# 2.net
KiCad netlist of a schematic drawn in Altium Designer
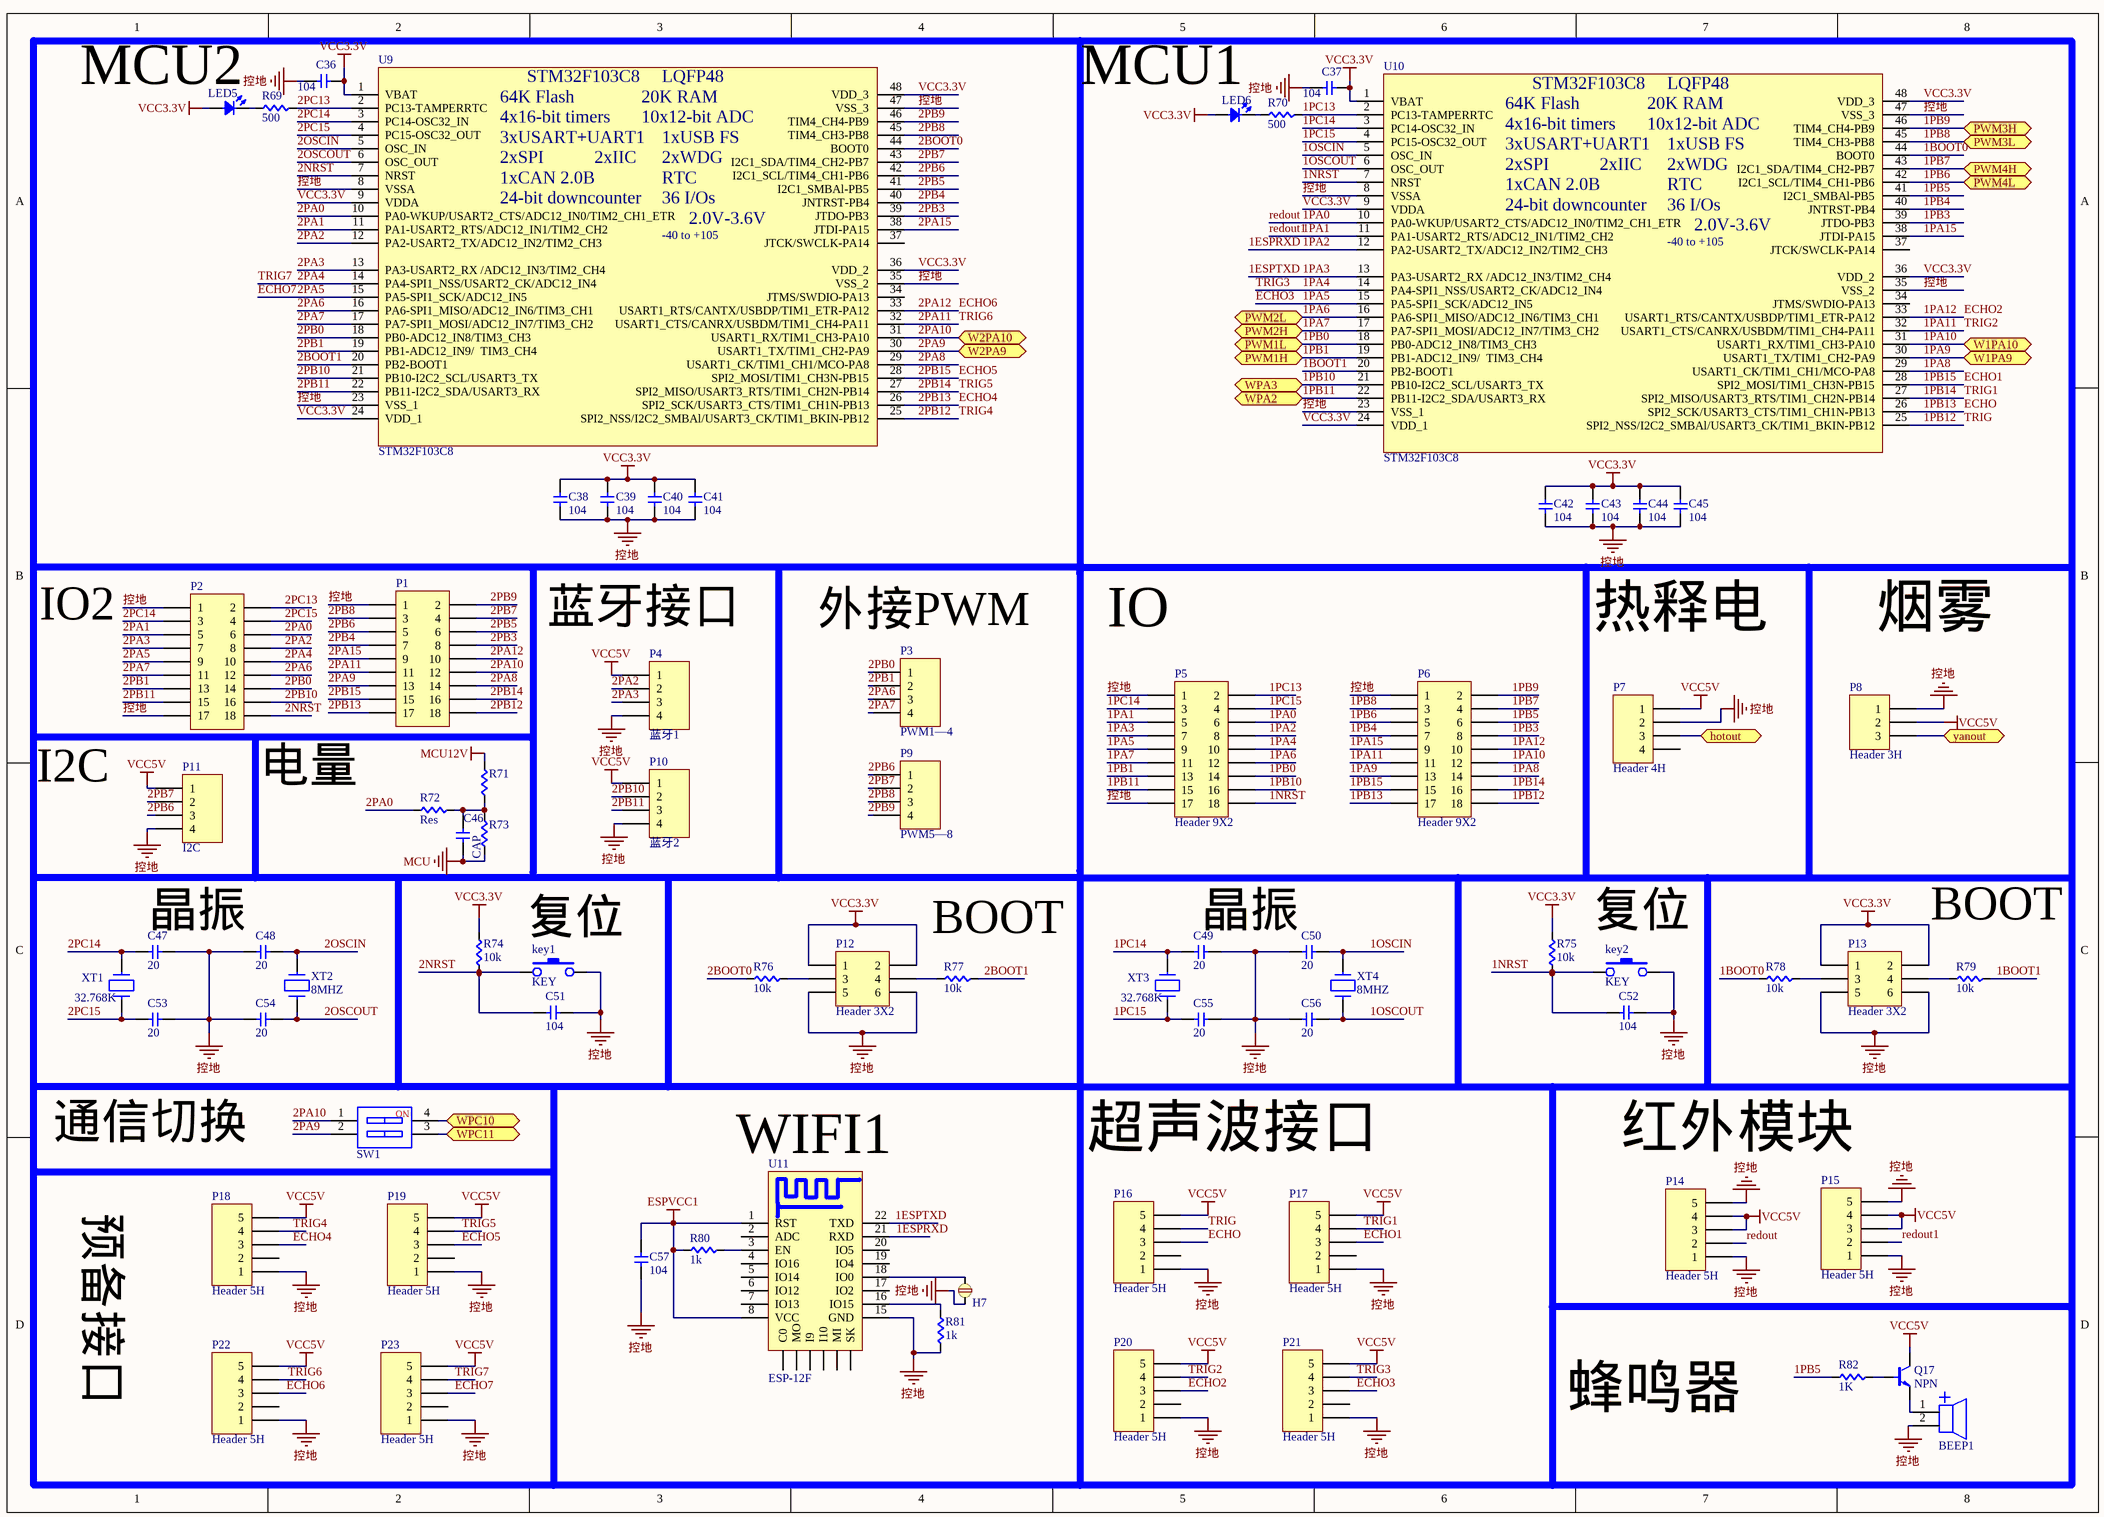
[diagram p0: 小车主板原理图2.SchDoc]

(export (version "E")
  (design (tool "Eeschema 10.0.6"))
  (components
    (comp (ref "BEEP1") (value "5V有源蜂鸣器") (footprint "5V蜂鸣器") (libsource (lib "史福祥库") (part "5V有源蜂鸣器")))
    (comp (ref "C36") (value "104") (footprint "0805C") (libsource (lib "史福祥库") (part "C")))
    (comp (ref "C37") (value "104") (footprint "0805C") (libsource (lib "史福祥库") (part "C")))
    (comp (ref "C38") (value "104") (footprint "0805C") (libsource (lib "史福祥库") (part "C")))
    (comp (ref "C39") (value "104") (footprint "0805C") (libsource (lib "史福祥库") (part "C")))
    (comp (ref "C40") (value "104") (footprint "0805C") (libsource (lib "史福祥库") (part "C")))
    (comp (ref "C41") (value "104") (footprint "0805C") (libsource (lib "史福祥库") (part "C")))
    (comp (ref "C42") (value "104") (footprint "0805C") (libsource (lib "史福祥库") (part "C")))
    (comp (ref "C43") (value "104") (footprint "0805C") (libsource (lib "史福祥库") (part "C")))
    (comp (ref "C44") (value "104") (footprint "0805C") (libsource (lib "史福祥库") (part "C")))
    (comp (ref "C45") (value "104") (footprint "0805C") (libsource (lib "史福祥库") (part "C")))
    (comp (ref "C46") (value "CAP") (footprint "0805C") (libsource (lib "史福祥库") (part "C")))
    (comp (ref "C47") (value "20") (footprint "0805C") (libsource (lib "史福祥库") (part "C")))
    (comp (ref "C48") (value "20") (footprint "0805C") (libsource (lib "史福祥库") (part "C")))
    (comp (ref "C49") (value "20") (footprint "0805C") (libsource (lib "史福祥库") (part "C")))
    (comp (ref "C50") (value "20") (footprint "0805C") (libsource (lib "史福祥库") (part "C")))
    (comp (ref "C51") (value "104") (footprint "0805C") (libsource (lib "史福祥库") (part "C")))
    (comp (ref "C52") (value "104") (footprint "0805C") (libsource (lib "史福祥库") (part "C")))
    (comp (ref "C53") (value "20") (footprint "0805C") (libsource (lib "史福祥库") (part "C")))
    (comp (ref "C54") (value "20") (footprint "0805C") (libsource (lib "史福祥库") (part "C")))
    (comp (ref "C55") (value "20") (footprint "0805C") (libsource (lib "史福祥库") (part "C")))
    (comp (ref "C56") (value "20") (footprint "0805C") (libsource (lib "史福祥库") (part "C")))
    (comp (ref "C57") (value "104") (footprint "0805C") (libsource (lib "史福祥库") (part "C")))
    (comp (ref "H7") (value "2脚") (footprint "2P") (libsource (lib "史福祥库") (part "2脚")))
    (comp (ref "key1") (value "KEY") (footprint "按键DIP-3*6*5") (libsource (lib "史福祥库") (part "KEY")))
    (comp (ref "key2") (value "KEY") (footprint "按键DIP-3*6*5") (libsource (lib "史福祥库") (part "KEY")))
    (comp (ref "LED5")
      (value "LED")
      (footprint "0805D")
      (fields (field (name "PUBLISHER") "Altium Limited"))
      (libsource (lib "史福祥库") (part "LED"))
    )
    (comp (ref "LED6")
      (value "LED")
      (footprint "0805D")
      (fields (field (name "PUBLISHER") "Altium Limited"))
      (libsource (lib "史福祥库") (part "LED"))
    )
    (comp (ref "P1")
      (value "~")
      (footprint "HDR2X9")
      (description "Header, 9-Pin, Dual row")
      (fields (field (name "PUBLISHER") "Altium Limited"))
      (libsource (lib "Miscellaneous Connectors") (part "Header 9X2"))
    )
    (comp (ref "P2")
      (value "~")
      (footprint "HDR2X9")
      (description "Header, 9-Pin, Dual row")
      (fields (field (name "PUBLISHER") "Altium Limited"))
      (libsource (lib "Miscellaneous Connectors") (part "Header 9X2"))
    )
    (comp (ref "P3")
      (value "PWM1—4")
      (footprint "PZ_XH-2.54-4P")
      (description "Header, 4-Pin, Right Angle")
      (fields (field (name "PUBLISHER") "Altium Limited"))
      (libsource (lib "") (part "Header 4H_1"))
    )
    (comp (ref "P4")
      (value "蓝牙1")
      (footprint "PZ_XH-2.54-4P")
      (description "Header, 4-Pin, Right Angle")
      (fields (field (name "PUBLISHER") "Altium Limited"))
      (libsource (lib "") (part "Header 4H_1"))
    )
    (comp (ref "P5")
      (value "Header 9X2")
      (footprint "HDR2X9")
      (description "Header, 9-Pin, Dual row")
      (fields (field (name "PUBLISHER") "Altium Limited"))
      (libsource (lib "Miscellaneous Connectors") (part "Header 9X2"))
    )
    (comp (ref "P6")
      (value "Header 9X2")
      (footprint "HDR2X9")
      (description "Header, 9-Pin, Dual row")
      (fields (field (name "PUBLISHER") "Altium Limited"))
      (libsource (lib "Miscellaneous Connectors") (part "Header 9X2"))
    )
    (comp (ref "P7")
      (value "Header 4H")
      (footprint "PZ_XH-2.54-4P")
      (description "Header, 4-Pin, Right Angle")
      (fields (field (name "PUBLISHER") "Altium Limited"))
      (libsource (lib "Miscellaneous Connectors") (part "Header 4H"))
    )
    (comp (ref "P8")
      (value "Header 3H")
      (footprint "PZ_XH-2.54-3P")
      (description "Header, 3-Pin, Right Angle")
      (fields (field (name "PUBLISHER") "Altium Limited"))
      (libsource (lib "Miscellaneous Connectors") (part "Header 3H"))
    )
    (comp (ref "P9")
      (value "PWM5—8")
      (footprint "PZ_XH-2.54-4P")
      (description "Header, 4-Pin, Right Angle")
      (fields (field (name "PUBLISHER") "Altium Limited"))
      (libsource (lib "") (part "Header 4H_1"))
    )
    (comp (ref "P10")
      (value "蓝牙2")
      (footprint "PZ_XH-2.54-4P")
      (description "Header, 4-Pin, Right Angle")
      (fields (field (name "PUBLISHER") "Altium Limited"))
      (libsource (lib "") (part "Header 4H_1"))
    )
    (comp (ref "P11")
      (value "I2C")
      (footprint "PZ_XH-2.54-4P")
      (description "Header, 4-Pin, Right Angle")
      (fields (field (name "PUBLISHER") "Altium Limited"))
      (libsource (lib "") (part "Header 4H_1"))
    )
    (comp (ref "P12")
      (value "Header 3X2")
      (footprint "HDR2X3")
      (description "Header, 3-Pin, Dual row")
      (fields (field (name "PUBLISHER") "Altium Limited"))
      (libsource (lib "Miscellaneous Connectors") (part "Header 3X2"))
    )
    (comp (ref "P13")
      (value "Header 3X2")
      (footprint "HDR2X3")
      (description "Header, 3-Pin, Dual row")
      (fields (field (name "PUBLISHER") "Altium Limited"))
      (libsource (lib "Miscellaneous Connectors") (part "Header 3X2"))
    )
    (comp (ref "P14")
      (value "Header 5H")
      (footprint "PZ_XH-2.54-5P")
      (description "Header, 5-Pin, Right Angle")
      (fields (field (name "PUBLISHER") "Altium Limited"))
      (libsource (lib "Miscellaneous Connectors") (part "Header 5H"))
    )
    (comp (ref "P15")
      (value "Header 5H")
      (footprint "PZ_XH-2.54-5P")
      (description "Header, 5-Pin, Right Angle")
      (fields (field (name "PUBLISHER") "Altium Limited"))
      (libsource (lib "Miscellaneous Connectors") (part "Header 5H"))
    )
    (comp (ref "P16")
      (value "Header 5H")
      (footprint "PZ_XH-2.54-5P")
      (description "Header, 5-Pin, Right Angle")
      (fields (field (name "PUBLISHER") "Altium Limited"))
      (libsource (lib "Miscellaneous Connectors") (part "Header 5H"))
    )
    (comp (ref "P17")
      (value "Header 5H")
      (footprint "PZ_XH-2.54-5P")
      (description "Header, 5-Pin, Right Angle")
      (fields (field (name "PUBLISHER") "Altium Limited"))
      (libsource (lib "Miscellaneous Connectors") (part "Header 5H"))
    )
    (comp (ref "P18")
      (value "Header 5H")
      (footprint "PZ_XH-2.54-5P")
      (description "Header, 5-Pin, Right Angle")
      (fields (field (name "PUBLISHER") "Altium Limited"))
      (libsource (lib "Miscellaneous Connectors") (part "Header 5H"))
    )
    (comp (ref "P19")
      (value "Header 5H")
      (footprint "PZ_XH-2.54-5P")
      (description "Header, 5-Pin, Right Angle")
      (fields (field (name "PUBLISHER") "Altium Limited"))
      (libsource (lib "Miscellaneous Connectors") (part "Header 5H"))
    )
    (comp (ref "P20")
      (value "Header 5H")
      (footprint "PZ_XH-2.54-5P")
      (description "Header, 5-Pin, Right Angle")
      (fields (field (name "PUBLISHER") "Altium Limited"))
      (libsource (lib "Miscellaneous Connectors") (part "Header 5H"))
    )
    (comp (ref "P21")
      (value "Header 5H")
      (footprint "PZ_XH-2.54-5P")
      (description "Header, 5-Pin, Right Angle")
      (fields (field (name "PUBLISHER") "Altium Limited"))
      (libsource (lib "Miscellaneous Connectors") (part "Header 5H"))
    )
    (comp (ref "P22")
      (value "Header 5H")
      (footprint "PZ_XH-2.54-5P")
      (description "Header, 5-Pin, Right Angle")
      (fields (field (name "PUBLISHER") "Altium Limited"))
      (libsource (lib "Miscellaneous Connectors") (part "Header 5H"))
    )
    (comp (ref "P23")
      (value "Header 5H")
      (footprint "PZ_XH-2.54-5P")
      (description "Header, 5-Pin, Right Angle")
      (fields (field (name "PUBLISHER") "Altium Limited"))
      (libsource (lib "Miscellaneous Connectors") (part "Header 5H"))
    )
    (comp (ref "Q17") (value "NPN") (footprint "SOT-23") (libsource (lib "史福祥库") (part "NPN")))
    (comp (ref "R69") (value "500") (footprint "0805") (libsource (lib "史福祥库") (part "Res")))
    (comp (ref "R70") (value "500") (footprint "0805") (libsource (lib "史福祥库") (part "Res")))
    (comp (ref "R71") (value "~") (footprint "0805") (libsource (lib "史福祥库") (part "Res")))
    (comp (ref "R72") (value "Res") (footprint "0805") (libsource (lib "史福祥库") (part "Res")))
    (comp (ref "R73") (value "~") (footprint "0805") (libsource (lib "史福祥库") (part "Res")))
    (comp (ref "R74") (value "10k") (footprint "0805") (libsource (lib "史福祥库") (part "Res")))
    (comp (ref "R75") (value "10k") (footprint "0805") (libsource (lib "史福祥库") (part "Res")))
    (comp (ref "R76") (value "10k") (footprint "0805") (libsource (lib "史福祥库") (part "Res")))
    (comp (ref "R77") (value "10k") (footprint "0805") (libsource (lib "史福祥库") (part "Res")))
    (comp (ref "R78") (value "10k") (footprint "0805") (libsource (lib "史福祥库") (part "Res")))
    (comp (ref "R79") (value "10k") (footprint "0805") (libsource (lib "史福祥库") (part "Res")))
    (comp (ref "R80") (value "1k") (footprint "0805") (libsource (lib "史福祥库") (part "Res")))
    (comp (ref "R81") (value "1k") (footprint "0805") (libsource (lib "史福祥库") (part "Res")))
    (comp (ref "R82") (value "1K") (footprint "0805") (libsource (lib "史福祥库") (part "Res")))
    (comp (ref "SW1")
      (value "CSW-2P")
      (footprint "CSW DIP-2P")
      (description "2路编码开关")
      (fields (field (name "版权归属") "源创客"))
      (libsource (lib "史福祥库") (part "CSW-2P"))
    )
    (comp (ref "U9") (value "STM32F103C8") (footprint "TQFP48") (libsource (lib "史福祥库") (part "STM32F103C8")))
    (comp (ref "U10")
      (value "STM32F103C8")
      (footprint "TQFP48")
      (libsource (lib "史福祥库") (part "STM32F103C8"))
    )
    (comp (ref "U11") (value "ESP-12F") (footprint "ESP-12F") (libsource (lib "史福祥库") (part "ESP-12F")))
    (comp (ref "XT1") (value "32.768K") (footprint "XTAL-T") (libsource (lib "史福祥库") (part "XTAL")))
    (comp (ref "XT2") (value "8MHZ") (footprint "XTAL-T") (libsource (lib "史福祥库") (part "XTAL")))
    (comp (ref "XT3") (value "32.768K") (footprint "XTAL-T") (libsource (lib "史福祥库") (part "XTAL")))
    (comp (ref "XT4") (value "8MHZ") (footprint "XTAL-T") (libsource (lib "史福祥库") (part "XTAL")))
  )
  (nets
    (net (code "1") (name "/1BOOT0") (class "Default")
      (node (ref "R78") (pin "2") (pinfunction "2_2") (pintype "passive"))
      (node (ref "U10") (pin "44") (pinfunction "BOOT0_44") (pintype "passive"))
    )
    (net (code "2") (name "/1BOOT1") (class "Default")
      (node (ref "R79") (pin "1") (pinfunction "1_1") (pintype "passive"))
      (node (ref "U10") (pin "20") (pinfunction "PB2-BOOT1_20") (pintype "passive"))
    )
    (net (code "3") (name "/1ESPRXD") (class "Default")
      (node (ref "P5") (pin "8") (pinfunction "8_8") (pintype "passive"))
      (node (ref "U10") (pin "12") (pinfunction "PA2-USART2_TX/ADC12_IN2/TIM2_CH3_12") (pintype "passive"))
      (node (ref "U11") (pin "21") (pinfunction "RXD_21") (pintype "passive"))
    )
    (net (code "4") (name "/1ESPTXD") (class "Default")
      (node (ref "P5") (pin "7") (pinfunction "7_7") (pintype "passive"))
      (node (ref "U10") (pin "13") (pinfunction "PA3-USART2_RX_/ADC12_IN3/TIM2_CH4_13") (pintype "passive"))
      (node (ref "U11") (pin "22") (pinfunction "TXD_22") (pintype "passive"))
    )
    (net (code "5") (name "/1NRST") (class "Default")
      (node (ref "C52") (pin "1") (pinfunction "1_1") (pintype "passive"))
      (node (ref "P5") (pin "18") (pinfunction "18_18") (pintype "passive"))
      (node (ref "R75") (pin "1") (pinfunction "1_1") (pintype "passive"))
      (node (ref "U10") (pin "7") (pinfunction "NRST_7") (pintype "passive"))
      (node (ref "key2") (pin "1") (pinfunction "1_1") (pintype "passive"))
    )
    (net (code "6") (name "/1OSCIN") (class "Default")
      (node (ref "C50") (pin "2") (pinfunction "2_2") (pintype "passive"))
      (node (ref "U10") (pin "5") (pinfunction "OSC_IN_5") (pintype "passive"))
      (node (ref "XT4") (pin "2") (pinfunction "2_2") (pintype "passive"))
    )
    (net (code "7") (name "/1OSCOUT") (class "Default")
      (node (ref "C56") (pin "2") (pinfunction "2_2") (pintype "passive"))
      (node (ref "U10") (pin "6") (pinfunction "OSC_OUT_6") (pintype "passive"))
      (node (ref "XT4") (pin "1") (pinfunction "1_1") (pintype "passive"))
    )
    (net (code "8") (name "/1PA0") (class "Default")
      (node (ref "P14") (pin "2") (pinfunction "2_2") (pintype "passive"))
      (node (ref "P5") (pin "6") (pinfunction "6_6") (pintype "passive"))
      (node (ref "U10") (pin "10") (pinfunction "PA0-WKUP/USART2_CTS/ADC12_IN0/TIM2_CH1_ETR_10") (pintype "passive"))
    )
    (net (code "9") (name "/1PA1") (class "Default")
      (node (ref "P15") (pin "2") (pinfunction "2_2") (pintype "passive"))
      (node (ref "P5") (pin "5") (pinfunction "5_5") (pintype "passive"))
      (node (ref "U10") (pin "11") (pinfunction "PA1-USART2_RTS/ADC12_IN1/TIM2_CH2_11") (pintype "passive"))
    )
    (net (code "10") (name "/1PA4") (class "Default")
      (node (ref "P21") (pin "4") (pinfunction "4_4") (pintype "passive"))
      (node (ref "P5") (pin "10") (pinfunction "10_10") (pintype "passive"))
      (node (ref "U10") (pin "14") (pinfunction "PA4-SPI1_NSS/USART2_CK/ADC12_IN4_14") (pintype "passive"))
    )
    (net (code "11") (name "/1PA5") (class "Default")
      (node (ref "P21") (pin "3") (pinfunction "3_3") (pintype "passive"))
      (node (ref "P5") (pin "9") (pinfunction "9_9") (pintype "passive"))
      (node (ref "U10") (pin "15") (pinfunction "PA5-SPI1_SCK/ADC12_IN5_15") (pintype "passive"))
    )
    (net (code "12") (name "/1PA6") (class "Default")
      (node (ref "P5") (pin "12") (pinfunction "12_12") (pintype "passive"))
      (node (ref "U10") (pin "16") (pinfunction "PA6-SPI1_MISO/ADC12_IN6/TIM3_CH1_16") (pintype "passive"))
    )
    (net (code "13") (name "/1PA7") (class "Default")
      (node (ref "P5") (pin "11") (pinfunction "11_11") (pintype "passive"))
      (node (ref "U10") (pin "17") (pinfunction "PA7-SPI1_MOSI/ADC12_IN7/TIM3_CH2_17") (pintype "passive"))
    )
    (net (code "14") (name "/1PA8") (class "Default")
      (node (ref "P6") (pin "14") (pinfunction "14_14") (pintype "passive"))
      (node (ref "U10") (pin "29") (pinfunction "USART1_CK/TIM1_CH1/MCO-PA8_29") (pintype "passive"))
    )
    (net (code "15") (name "/1PA9") (class "Default")
      (node (ref "P6") (pin "13") (pinfunction "13_13") (pintype "passive"))
      (node (ref "U10") (pin "30") (pinfunction "USART1_TX/TIM1_CH2-PA9_30") (pintype "passive"))
    )
    (net (code "16") (name "/1PA10") (class "Default")
      (node (ref "P6") (pin "12") (pinfunction "12_12") (pintype "passive"))
      (node (ref "U10") (pin "31") (pinfunction "USART1_RX/TIM1_CH3-PA10_31") (pintype "passive"))
    )
    (net (code "17") (name "/1PA11") (class "Default")
      (node (ref "P20") (pin "4") (pinfunction "4_4") (pintype "passive"))
      (node (ref "P6") (pin "11") (pinfunction "11_11") (pintype "passive"))
      (node (ref "U10") (pin "32") (pinfunction "USART1_CTS/CANRX/USBDM/TIM1_CH4-PA11_32") (pintype "passive"))
    )
    (net (code "18") (name "/1PA12") (class "Default")
      (node (ref "P20") (pin "3") (pinfunction "3_3") (pintype "passive"))
      (node (ref "P6") (pin "10") (pinfunction "10_10") (pintype "passive"))
      (node (ref "U10") (pin "33") (pinfunction "USART1_RTS/CANTX/USBDP/TIM1_ETR-PA12_33") (pintype "passive"))
    )
    (net (code "19") (name "/1PA15") (class "Default")
      (node (ref "P6") (pin "9") (pinfunction "9_9") (pintype "passive"))
      (node (ref "U10") (pin "38") (pinfunction "JTDI-PA15_38") (pintype "passive"))
    )
    (net (code "20") (name "/1PB0") (class "Default")
      (node (ref "P5") (pin "14") (pinfunction "14_14") (pintype "passive"))
      (node (ref "U10") (pin "18") (pinfunction "PB0-ADC12_IN8/TIM3_CH3_18") (pintype "passive"))
    )
    (net (code "21") (name "/1PB1") (class "Default")
      (node (ref "P5") (pin "13") (pinfunction "13_13") (pintype "passive"))
      (node (ref "U10") (pin "19") (pinfunction "PB1-ADC12_IN9/__TIM3_CH4_19") (pintype "passive"))
    )
    (net (code "22") (name "/1PB3") (class "Default")
      (node (ref "P6") (pin "8") (pinfunction "8_8") (pintype "passive"))
      (node (ref "U10") (pin "39") (pinfunction "JTDO-PB3_39") (pintype "passive"))
    )
    (net (code "23") (name "/1PB4") (class "Default")
      (node (ref "P6") (pin "7") (pinfunction "7_7") (pintype "passive"))
      (node (ref "U10") (pin "40") (pinfunction "JNTRST-PB4_40") (pintype "passive"))
    )
    (net (code "24") (name "/1PB5") (class "Default")
      (node (ref "P6") (pin "6") (pinfunction "6_6") (pintype "passive"))
      (node (ref "R82") (pin "1") (pinfunction "1_1") (pintype "passive"))
      (node (ref "U10") (pin "41") (pinfunction "I2C1_SMBAl-PB5_41") (pintype "passive"))
    )
    (net (code "25") (name "/1PB6") (class "Default")
      (node (ref "P6") (pin "5") (pinfunction "5_5") (pintype "passive"))
      (node (ref "U10") (pin "42") (pinfunction "I2C1_SCL/TIM4_CH1-PB6_42") (pintype "passive"))
    )
    (net (code "26") (name "/1PB7") (class "Default")
      (node (ref "P6") (pin "4") (pinfunction "4_4") (pintype "passive"))
      (node (ref "U10") (pin "43") (pinfunction "I2C1_SDA/TIM4_CH2-PB7_43") (pintype "passive"))
    )
    (net (code "27") (name "/1PB8") (class "Default")
      (node (ref "P6") (pin "3") (pinfunction "3_3") (pintype "passive"))
      (node (ref "U10") (pin "45") (pinfunction "TIM4_CH3-PB8_45") (pintype "passive"))
    )
    (net (code "28") (name "/1PB9") (class "Default")
      (node (ref "P6") (pin "2") (pinfunction "2_2") (pintype "passive"))
      (node (ref "U10") (pin "46") (pinfunction "TIM4_CH4-PB9_46") (pintype "passive"))
    )
    (net (code "29") (name "/1PB10") (class "Default")
      (node (ref "P5") (pin "16") (pinfunction "16_16") (pintype "passive"))
      (node (ref "U10") (pin "21") (pinfunction "PB10-I2C2_SCL/USART3_TX_21") (pintype "passive"))
    )
    (net (code "30") (name "/1PB11") (class "Default")
      (node (ref "P5") (pin "15") (pinfunction "15_15") (pintype "passive"))
      (node (ref "U10") (pin "22") (pinfunction "PB11-I2C2_SDA/USART3_RX_22") (pintype "passive"))
    )
    (net (code "31") (name "/1PB12") (class "Default")
      (node (ref "P16") (pin "4") (pinfunction "4_4") (pintype "passive"))
      (node (ref "P6") (pin "18") (pinfunction "18_18") (pintype "passive"))
      (node (ref "U10") (pin "25") (pinfunction "SPI2_NSS/I2C2_SMBAl/USART3_CK/TIM1_BKIN-PB12_25") (pintype "passive"))
    )
    (net (code "32") (name "/1PB13") (class "Default")
      (node (ref "P16") (pin "3") (pinfunction "3_3") (pintype "passive"))
      (node (ref "P6") (pin "17") (pinfunction "17_17") (pintype "passive"))
      (node (ref "U10") (pin "26") (pinfunction "SPI2_SCK/USART3_CTS/TIM1_CH1N-PB13_26") (pintype "passive"))
    )
    (net (code "33") (name "/1PB14") (class "Default")
      (node (ref "P17") (pin "4") (pinfunction "4_4") (pintype "passive"))
      (node (ref "P6") (pin "16") (pinfunction "16_16") (pintype "passive"))
      (node (ref "U10") (pin "27") (pinfunction "SPI2_MISO/USART3_RTS/TIM1_CH2N-PB14_27") (pintype "passive"))
    )
    (net (code "34") (name "/1PB15") (class "Default")
      (node (ref "P17") (pin "3") (pinfunction "3_3") (pintype "passive"))
      (node (ref "P6") (pin "15") (pinfunction "15_15") (pintype "passive"))
      (node (ref "U10") (pin "28") (pinfunction "SPI2_MOSI/TIM1_CH3N-PB15_28") (pintype "passive"))
    )
    (net (code "35") (name "/1PC13") (class "Default")
      (node (ref "P5") (pin "2") (pinfunction "2_2") (pintype "passive"))
      (node (ref "R70") (pin "2") (pinfunction "2_2") (pintype "passive"))
      (node (ref "U10") (pin "2") (pinfunction "PC13-TAMPERRTC_2") (pintype "passive"))
    )
    (net (code "36") (name "/1PC14") (class "Default")
      (node (ref "C49") (pin "2") (pinfunction "2_2") (pintype "passive"))
      (node (ref "P5") (pin "3") (pinfunction "3_3") (pintype "passive"))
      (node (ref "U10") (pin "3") (pinfunction "PC14-OSC32_IN_3") (pintype "passive"))
      (node (ref "XT3") (pin "1") (pinfunction "1_1") (pintype "passive"))
    )
    (net (code "37") (name "/1PC15") (class "Default")
      (node (ref "C55") (pin "2") (pinfunction "2_2") (pintype "passive"))
      (node (ref "P5") (pin "4") (pinfunction "4_4") (pintype "passive"))
      (node (ref "U10") (pin "4") (pinfunction "PC15-OSC32_OUT_4") (pintype "passive"))
      (node (ref "XT3") (pin "2") (pinfunction "2_2") (pintype "passive"))
    )
    (net (code "38") (name "/2BOOT0") (class "Default")
      (node (ref "R76") (pin "2") (pinfunction "2_2") (pintype "passive"))
      (node (ref "U9") (pin "44") (pinfunction "BOOT0_44") (pintype "passive"))
    )
    (net (code "39") (name "/2BOOT1") (class "Default")
      (node (ref "R77") (pin "1") (pinfunction "1_1") (pintype "passive"))
      (node (ref "U9") (pin "20") (pinfunction "PB2-BOOT1_20") (pintype "passive"))
    )
    (net (code "40") (name "/2NRST") (class "Default")
      (node (ref "C51") (pin "1") (pinfunction "1_1") (pintype "passive"))
      (node (ref "P2") (pin "18") (pinfunction "18_18") (pintype "passive"))
      (node (ref "R74") (pin "1") (pinfunction "1_1") (pintype "passive"))
      (node (ref "U9") (pin "7") (pinfunction "NRST_7") (pintype "passive"))
      (node (ref "key1") (pin "1") (pinfunction "1_1") (pintype "passive"))
    )
    (net (code "41") (name "/2OSCIN") (class "Default")
      (node (ref "C48") (pin "2") (pinfunction "2_2") (pintype "passive"))
      (node (ref "U9") (pin "5") (pinfunction "OSC_IN_5") (pintype "passive"))
      (node (ref "XT2") (pin "2") (pinfunction "2_2") (pintype "passive"))
    )
    (net (code "42") (name "/2OSCOUT") (class "Default")
      (node (ref "C54") (pin "2") (pinfunction "2_2") (pintype "passive"))
      (node (ref "U9") (pin "6") (pinfunction "OSC_OUT_6") (pintype "passive"))
      (node (ref "XT2") (pin "1") (pinfunction "1_1") (pintype "passive"))
    )
    (net (code "43") (name "/2PA0") (class "Default")
      (node (ref "P2") (pin "6") (pinfunction "6_6") (pintype "passive"))
      (node (ref "R72") (pin "2") (pinfunction "2_2") (pintype "passive"))
      (node (ref "U9") (pin "10") (pinfunction "PA0-WKUP/USART2_CTS/ADC12_IN0/TIM2_CH1_ETR_10") (pintype "passive"))
    )
    (net (code "44") (name "/2PA1") (class "Default")
      (node (ref "P2") (pin "5") (pinfunction "5_5") (pintype "passive"))
      (node (ref "U9") (pin "11") (pinfunction "PA1-USART2_RTS/ADC12_IN1/TIM2_CH2_11") (pintype "passive"))
    )
    (net (code "45") (name "/2PA2") (class "Default")
      (node (ref "P2") (pin "8") (pinfunction "8_8") (pintype "passive"))
      (node (ref "P4") (pin "2") (pinfunction "2_2") (pintype "passive"))
      (node (ref "U9") (pin "12") (pinfunction "PA2-USART2_TX/ADC12_IN2/TIM2_CH3_12") (pintype "passive"))
    )
    (net (code "46") (name "/2PA3") (class "Default")
      (node (ref "P2") (pin "7") (pinfunction "7_7") (pintype "passive"))
      (node (ref "P4") (pin "3") (pinfunction "3_3") (pintype "passive"))
      (node (ref "U9") (pin "13") (pinfunction "PA3-USART2_RX_/ADC12_IN3/TIM2_CH4_13") (pintype "passive"))
    )
    (net (code "47") (name "/2PA4") (class "Default")
      (node (ref "P2") (pin "10") (pinfunction "10_10") (pintype "passive"))
      (node (ref "P23") (pin "4") (pinfunction "4_4") (pintype "passive"))
      (node (ref "U9") (pin "14") (pinfunction "PA4-SPI1_NSS/USART2_CK/ADC12_IN4_14") (pintype "passive"))
    )
    (net (code "48") (name "/2PA5") (class "Default")
      (node (ref "P2") (pin "9") (pinfunction "9_9") (pintype "passive"))
      (node (ref "P23") (pin "3") (pinfunction "3_3") (pintype "passive"))
      (node (ref "U9") (pin "15") (pinfunction "PA5-SPI1_SCK/ADC12_IN5_15") (pintype "passive"))
    )
    (net (code "49") (name "/2PA6") (class "Default")
      (node (ref "P2") (pin "12") (pinfunction "12_12") (pintype "passive"))
      (node (ref "P3") (pin "3") (pinfunction "3_3") (pintype "passive"))
      (node (ref "U9") (pin "16") (pinfunction "PA6-SPI1_MISO/ADC12_IN6/TIM3_CH1_16") (pintype "passive"))
    )
    (net (code "50") (name "/2PA7") (class "Default")
      (node (ref "P2") (pin "11") (pinfunction "11_11") (pintype "passive"))
      (node (ref "P3") (pin "4") (pinfunction "4_4") (pintype "passive"))
      (node (ref "U9") (pin "17") (pinfunction "PA7-SPI1_MOSI/ADC12_IN7/TIM3_CH2_17") (pintype "passive"))
    )
    (net (code "51") (name "/2PA8") (class "Default")
      (node (ref "P1") (pin "14") (pinfunction "14_14") (pintype "passive"))
      (node (ref "U9") (pin "29") (pinfunction "USART1_CK/TIM1_CH1/MCO-PA8_29") (pintype "passive"))
    )
    (net (code "52") (name "/2PA9") (class "Default")
      (node (ref "P1") (pin "13") (pinfunction "13_13") (pintype "passive"))
      (node (ref "SW1") (pin "2") (pinfunction "2_2") (pintype "passive"))
      (node (ref "U9") (pin "30") (pinfunction "USART1_TX/TIM1_CH2-PA9_30") (pintype "passive"))
    )
    (net (code "53") (name "/2PA10") (class "Default")
      (node (ref "P1") (pin "12") (pinfunction "12_12") (pintype "passive"))
      (node (ref "SW1") (pin "1") (pinfunction "1_1") (pintype "passive"))
      (node (ref "U9") (pin "31") (pinfunction "USART1_RX/TIM1_CH3-PA10_31") (pintype "passive"))
    )
    (net (code "54") (name "/2PA11") (class "Default")
      (node (ref "P1") (pin "11") (pinfunction "11_11") (pintype "passive"))
      (node (ref "P22") (pin "4") (pinfunction "4_4") (pintype "passive"))
      (node (ref "U9") (pin "32") (pinfunction "USART1_CTS/CANRX/USBDM/TIM1_CH4-PA11_32") (pintype "passive"))
    )
    (net (code "55") (name "/2PA12") (class "Default")
      (node (ref "P1") (pin "10") (pinfunction "10_10") (pintype "passive"))
      (node (ref "P22") (pin "3") (pinfunction "3_3") (pintype "passive"))
      (node (ref "U9") (pin "33") (pinfunction "USART1_RTS/CANTX/USBDP/TIM1_ETR-PA12_33") (pintype "passive"))
    )
    (net (code "56") (name "/2PA15") (class "Default")
      (node (ref "P1") (pin "9") (pinfunction "9_9") (pintype "passive"))
      (node (ref "U9") (pin "38") (pinfunction "JTDI-PA15_38") (pintype "passive"))
    )
    (net (code "57") (name "/2PB0") (class "Default")
      (node (ref "P2") (pin "14") (pinfunction "14_14") (pintype "passive"))
      (node (ref "P3") (pin "1") (pinfunction "1_1") (pintype "passive"))
      (node (ref "U9") (pin "18") (pinfunction "PB0-ADC12_IN8/TIM3_CH3_18") (pintype "passive"))
    )
    (net (code "58") (name "/2PB1") (class "Default")
      (node (ref "P2") (pin "13") (pinfunction "13_13") (pintype "passive"))
      (node (ref "P3") (pin "2") (pinfunction "2_2") (pintype "passive"))
      (node (ref "U9") (pin "19") (pinfunction "PB1-ADC12_IN9/__TIM3_CH4_19") (pintype "passive"))
    )
    (net (code "59") (name "/2PB3") (class "Default")
      (node (ref "P1") (pin "8") (pinfunction "8_8") (pintype "passive"))
      (node (ref "U9") (pin "39") (pinfunction "JTDO-PB3_39") (pintype "passive"))
    )
    (net (code "60") (name "/2PB4") (class "Default")
      (node (ref "P1") (pin "7") (pinfunction "7_7") (pintype "passive"))
      (node (ref "U9") (pin "40") (pinfunction "JNTRST-PB4_40") (pintype "passive"))
    )
    (net (code "61") (name "/2PB5") (class "Default")
      (node (ref "P1") (pin "6") (pinfunction "6_6") (pintype "passive"))
      (node (ref "U9") (pin "41") (pinfunction "I2C1_SMBAl-PB5_41") (pintype "passive"))
    )
    (net (code "62") (name "/2PB6") (class "Default")
      (node (ref "P1") (pin "5") (pinfunction "5_5") (pintype "passive"))
      (node (ref "P11") (pin "3") (pinfunction "3_3") (pintype "passive"))
      (node (ref "P9") (pin "1") (pinfunction "1_1") (pintype "passive"))
      (node (ref "U9") (pin "42") (pinfunction "I2C1_SCL/TIM4_CH1-PB6_42") (pintype "passive"))
    )
    (net (code "63") (name "/2PB7") (class "Default")
      (node (ref "P1") (pin "4") (pinfunction "4_4") (pintype "passive"))
      (node (ref "P11") (pin "2") (pinfunction "2_2") (pintype "passive"))
      (node (ref "P9") (pin "2") (pinfunction "2_2") (pintype "passive"))
      (node (ref "U9") (pin "43") (pinfunction "I2C1_SDA/TIM4_CH2-PB7_43") (pintype "passive"))
    )
    (net (code "64") (name "/2PB8") (class "Default")
      (node (ref "P1") (pin "3") (pinfunction "3_3") (pintype "passive"))
      (node (ref "P9") (pin "3") (pinfunction "3_3") (pintype "passive"))
      (node (ref "U9") (pin "45") (pinfunction "TIM4_CH3-PB8_45") (pintype "passive"))
    )
    (net (code "65") (name "/2PB9") (class "Default")
      (node (ref "P1") (pin "2") (pinfunction "2_2") (pintype "passive"))
      (node (ref "P9") (pin "4") (pinfunction "4_4") (pintype "passive"))
      (node (ref "U9") (pin "46") (pinfunction "TIM4_CH4-PB9_46") (pintype "passive"))
    )
    (net (code "66") (name "/2PB10") (class "Default")
      (node (ref "P10") (pin "2") (pinfunction "2_2") (pintype "passive"))
      (node (ref "P2") (pin "16") (pinfunction "16_16") (pintype "passive"))
      (node (ref "U9") (pin "21") (pinfunction "PB10-I2C2_SCL/USART3_TX_21") (pintype "passive"))
    )
    (net (code "67") (name "/2PB11") (class "Default")
      (node (ref "P10") (pin "3") (pinfunction "3_3") (pintype "passive"))
      (node (ref "P2") (pin "15") (pinfunction "15_15") (pintype "passive"))
      (node (ref "U9") (pin "22") (pinfunction "PB11-I2C2_SDA/USART3_RX_22") (pintype "passive"))
    )
    (net (code "68") (name "/2PB12") (class "Default")
      (node (ref "P1") (pin "18") (pinfunction "18_18") (pintype "passive"))
      (node (ref "P18") (pin "4") (pinfunction "4_4") (pintype "passive"))
      (node (ref "U9") (pin "25") (pinfunction "SPI2_NSS/I2C2_SMBAl/USART3_CK/TIM1_BKIN-PB12_25") (pintype "passive"))
    )
    (net (code "69") (name "/2PB13") (class "Default")
      (node (ref "P1") (pin "17") (pinfunction "17_17") (pintype "passive"))
      (node (ref "P18") (pin "3") (pinfunction "3_3") (pintype "passive"))
      (node (ref "U9") (pin "26") (pinfunction "SPI2_SCK/USART3_CTS/TIM1_CH1N-PB13_26") (pintype "passive"))
    )
    (net (code "70") (name "/2PB14") (class "Default")
      (node (ref "P1") (pin "16") (pinfunction "16_16") (pintype "passive"))
      (node (ref "P19") (pin "4") (pinfunction "4_4") (pintype "passive"))
      (node (ref "U9") (pin "27") (pinfunction "SPI2_MISO/USART3_RTS/TIM1_CH2N-PB14_27") (pintype "passive"))
    )
    (net (code "71") (name "/2PB15") (class "Default")
      (node (ref "P1") (pin "15") (pinfunction "15_15") (pintype "passive"))
      (node (ref "P19") (pin "3") (pinfunction "3_3") (pintype "passive"))
      (node (ref "U9") (pin "28") (pinfunction "SPI2_MOSI/TIM1_CH3N-PB15_28") (pintype "passive"))
    )
    (net (code "72") (name "/2PC13") (class "Default")
      (node (ref "P2") (pin "2") (pinfunction "2_2") (pintype "passive"))
      (node (ref "R69") (pin "2") (pinfunction "2_2") (pintype "passive"))
      (node (ref "U9") (pin "2") (pinfunction "PC13-TAMPERRTC_2") (pintype "passive"))
    )
    (net (code "73") (name "/2PC14") (class "Default")
      (node (ref "C47") (pin "2") (pinfunction "2_2") (pintype "passive"))
      (node (ref "P2") (pin "3") (pinfunction "3_3") (pintype "passive"))
      (node (ref "U9") (pin "3") (pinfunction "PC14-OSC32_IN_3") (pintype "passive"))
      (node (ref "XT1") (pin "1") (pinfunction "1_1") (pintype "passive"))
    )
    (net (code "74") (name "/2PC15") (class "Default")
      (node (ref "C53") (pin "2") (pinfunction "2_2") (pintype "passive"))
      (node (ref "P2") (pin "4") (pinfunction "4_4") (pintype "passive"))
      (node (ref "U9") (pin "4") (pinfunction "PC15-OSC32_OUT_4") (pintype "passive"))
      (node (ref "XT1") (pin "2") (pinfunction "2_2") (pintype "passive"))
    )
    (net (code "75") (name "/WPC10") (class "Default")
      (node (ref "SW1") (pin "4") (pinfunction "4_4") (pintype "passive"))
    )
    (net (code "76") (name "/WPC11") (class "Default")
      (node (ref "SW1") (pin "3") (pinfunction "3_3") (pintype "passive"))
    )
    (net (code "77") (name "/hotout") (class "Default")
      (node (ref "P7") (pin "3") (pinfunction "3_3") (pintype "passive"))
    )
    (net (code "78") (name "/yanout") (class "Default")
      (node (ref "P8") (pin "3") (pinfunction "3_3") (pintype "passive"))
    )
    (net (code "79") (name "ESPVCC1") (class "Default")
      (node (ref "C57") (pin "2") (pinfunction "2_2") (pintype "passive"))
      (node (ref "R80") (pin "1") (pinfunction "1_1") (pintype "passive"))
      (node (ref "U11") (pin "1") (pinfunction "RST_1") (pintype "passive"))
      (node (ref "U11") (pin "8") (pinfunction "VCC_8") (pintype "passive"))
    )
    (net (code "80") (name "MCU") (class "Default")
      (node (ref "C46") (pin "1") (pinfunction "1_1") (pintype "passive"))
      (node (ref "R73") (pin "1") (pinfunction "1_1") (pintype "passive"))
    )
    (net (code "81") (name "MCU12V") (class "Default")
      (node (ref "R71") (pin "2") (pinfunction "2_2") (pintype "passive"))
    )
    (net (code "82") (name "Net-(BEEP1-VCC)") (class "Default")
      (node (ref "BEEP1") (pin "1") (pinfunction "VCC_1") (pintype "passive"))
      (node (ref "Q17") (pin "2") (pinfunction "e_2") (pintype "passive"))
    )
    (net (code "83") (name "Net-(C46-Pad2)") (class "Default")
      (node (ref "C46") (pin "2") (pinfunction "2_2") (pintype "passive"))
      (node (ref "R71") (pin "1") (pinfunction "1_1") (pintype "passive"))
      (node (ref "R72") (pin "1") (pinfunction "1_1") (pintype "passive"))
      (node (ref "R73") (pin "2") (pinfunction "2_2") (pintype "passive"))
    )
    (net (code "84") (name "Net-(LED5-K)") (class "Default")
      (node (ref "LED5") (pin "2") (pinfunction "K_2") (pintype "passive"))
      (node (ref "R69") (pin "1") (pinfunction "1_1") (pintype "passive"))
    )
    (net (code "85") (name "Net-(LED6-K)") (class "Default")
      (node (ref "LED6") (pin "2") (pinfunction "K_2") (pintype "passive"))
      (node (ref "R70") (pin "1") (pinfunction "1_1") (pintype "passive"))
    )
    (net (code "86") (name "Net-(P12-Pad3)") (class "Default")
      (node (ref "P12") (pin "3") (pinfunction "3_3") (pintype "passive"))
      (node (ref "R76") (pin "1") (pinfunction "1_1") (pintype "passive"))
    )
    (net (code "87") (name "Net-(P12-Pad4)") (class "Default")
      (node (ref "P12") (pin "4") (pinfunction "4_4") (pintype "passive"))
      (node (ref "R77") (pin "2") (pinfunction "2_2") (pintype "passive"))
    )
    (net (code "88") (name "Net-(P13-Pad3)") (class "Default")
      (node (ref "P13") (pin "3") (pinfunction "3_3") (pintype "passive"))
      (node (ref "R78") (pin "1") (pinfunction "1_1") (pintype "passive"))
    )
    (net (code "89") (name "Net-(P13-Pad4)") (class "Default")
      (node (ref "P13") (pin "4") (pinfunction "4_4") (pintype "passive"))
      (node (ref "R79") (pin "2") (pinfunction "2_2") (pintype "passive"))
    )
    (net (code "90") (name "Net-(Q17-b)") (class "Default")
      (node (ref "Q17") (pin "3") (pinfunction "b_3") (pintype "passive"))
      (node (ref "R82") (pin "2") (pinfunction "2_2") (pintype "passive"))
    )
    (net (code "91") (name "Net-(U11-EN)") (class "Default")
      (node (ref "R80") (pin "2") (pinfunction "2_2") (pintype "passive"))
      (node (ref "U11") (pin "3") (pinfunction "EN_3") (pintype "passive"))
    )
    (net (code "92") (name "Net-(U11-IO0)") (class "Default")
      (node (ref "H7") (pin "2") (pintype "passive"))
      (node (ref "U11") (pin "18") (pinfunction "IO0_18") (pintype "passive"))
    )
    (net (code "93") (name "Net-(U11-IO15)") (class "Default")
      (node (ref "R81") (pin "2") (pinfunction "2_2") (pintype "passive"))
      (node (ref "U11") (pin "16") (pinfunction "IO15_16") (pintype "passive"))
    )
    (net (code "94") (name "VCC3.3V") (class "Default")
      (node (ref "C36") (pin "2") (pinfunction "2_2") (pintype "passive"))
      (node (ref "C37") (pin "2") (pinfunction "2_2") (pintype "passive"))
      (node (ref "C38") (pin "2") (pinfunction "2_2") (pintype "passive"))
      (node (ref "C39") (pin "2") (pinfunction "2_2") (pintype "passive"))
      (node (ref "C40") (pin "2") (pinfunction "2_2") (pintype "passive"))
      (node (ref "C41") (pin "2") (pinfunction "2_2") (pintype "passive"))
      (node (ref "C42") (pin "2") (pinfunction "2_2") (pintype "passive"))
      (node (ref "C43") (pin "2") (pinfunction "2_2") (pintype "passive"))
      (node (ref "C44") (pin "2") (pinfunction "2_2") (pintype "passive"))
      (node (ref "C45") (pin "2") (pinfunction "2_2") (pintype "passive"))
      (node (ref "LED5") (pin "1") (pinfunction "A_1") (pintype "passive"))
      (node (ref "LED6") (pin "1") (pinfunction "A_1") (pintype "passive"))
      (node (ref "P12") (pin "1") (pinfunction "1_1") (pintype "passive"))
      (node (ref "P12") (pin "2") (pinfunction "2_2") (pintype "passive"))
      (node (ref "P13") (pin "1") (pinfunction "1_1") (pintype "passive"))
      (node (ref "P13") (pin "2") (pinfunction "2_2") (pintype "passive"))
      (node (ref "R74") (pin "2") (pinfunction "2_2") (pintype "passive"))
      (node (ref "R75") (pin "2") (pinfunction "2_2") (pintype "passive"))
      (node (ref "U10") (pin "1") (pinfunction "VBAT_1") (pintype "passive"))
      (node (ref "U10") (pin "24") (pinfunction "VDD_1_24") (pintype "passive"))
      (node (ref "U10") (pin "36") (pinfunction "VDD_2_36") (pintype "passive"))
      (node (ref "U10") (pin "48") (pinfunction "VDD_3_48") (pintype "passive"))
      (node (ref "U10") (pin "9") (pinfunction "VDDA_9") (pintype "passive"))
      (node (ref "U9") (pin "1") (pinfunction "VBAT_1") (pintype "passive"))
      (node (ref "U9") (pin "24") (pinfunction "VDD_1_24") (pintype "passive"))
      (node (ref "U9") (pin "36") (pinfunction "VDD_2_36") (pintype "passive"))
      (node (ref "U9") (pin "48") (pinfunction "VDD_3_48") (pintype "passive"))
      (node (ref "U9") (pin "9") (pinfunction "VDDA_9") (pintype "passive"))
    )
    (net (code "95") (name "VCC5V") (class "Default")
      (node (ref "P10") (pin "1") (pinfunction "1_1") (pintype "passive"))
      (node (ref "P11") (pin "1") (pinfunction "1_1") (pintype "passive"))
      (node (ref "P14") (pin "3") (pinfunction "3_3") (pintype "passive"))
      (node (ref "P14") (pin "4") (pinfunction "4_4") (pintype "passive"))
      (node (ref "P15") (pin "3") (pinfunction "3_3") (pintype "passive"))
      (node (ref "P15") (pin "4") (pinfunction "4_4") (pintype "passive"))
      (node (ref "P16") (pin "5") (pinfunction "5_5") (pintype "passive"))
      (node (ref "P17") (pin "5") (pinfunction "5_5") (pintype "passive"))
      (node (ref "P18") (pin "5") (pinfunction "5_5") (pintype "passive"))
      (node (ref "P19") (pin "5") (pinfunction "5_5") (pintype "passive"))
      (node (ref "P20") (pin "5") (pinfunction "5_5") (pintype "passive"))
      (node (ref "P21") (pin "5") (pinfunction "5_5") (pintype "passive"))
      (node (ref "P22") (pin "5") (pinfunction "5_5") (pintype "passive"))
      (node (ref "P23") (pin "5") (pinfunction "5_5") (pintype "passive"))
      (node (ref "P4") (pin "1") (pinfunction "1_1") (pintype "passive"))
      (node (ref "P7") (pin "1") (pinfunction "1_1") (pintype "passive"))
      (node (ref "P8") (pin "2") (pinfunction "2_2") (pintype "passive"))
      (node (ref "Q17") (pin "1") (pinfunction "c_1") (pintype "passive"))
    )
    (net (code "96") (name "unconnected-(P7-Pad4)") (class "Default")
      (node (ref "P7") (pin "4") (pinfunction "4_4") (pintype "passive"))
    )
    (net (code "97") (name "unconnected-(P16-Pad2)") (class "Default")
      (node (ref "P16") (pin "2") (pinfunction "2_2") (pintype "passive"))
    )
    (net (code "98") (name "unconnected-(P17-Pad2)") (class "Default")
      (node (ref "P17") (pin "2") (pinfunction "2_2") (pintype "passive"))
    )
    (net (code "99") (name "unconnected-(P18-Pad2)") (class "Default")
      (node (ref "P18") (pin "2") (pinfunction "2_2") (pintype "passive"))
    )
    (net (code "100") (name "unconnected-(P19-Pad2)") (class "Default")
      (node (ref "P19") (pin "2") (pinfunction "2_2") (pintype "passive"))
    )
    (net (code "101") (name "unconnected-(P20-Pad2)") (class "Default")
      (node (ref "P20") (pin "2") (pinfunction "2_2") (pintype "passive"))
    )
    (net (code "102") (name "unconnected-(P21-Pad2)") (class "Default")
      (node (ref "P21") (pin "2") (pinfunction "2_2") (pintype "passive"))
    )
    (net (code "103") (name "unconnected-(P22-Pad2)") (class "Default")
      (node (ref "P22") (pin "2") (pinfunction "2_2") (pintype "passive"))
    )
    (net (code "104") (name "unconnected-(P23-Pad2)") (class "Default")
      (node (ref "P23") (pin "2") (pinfunction "2_2") (pintype "passive"))
    )
    (net (code "105") (name "unconnected-(U9-JTCK{slash}SWCLK-PA14-Pad37)") (class "Default")
      (node (ref "U9") (pin "37") (pinfunction "JTCK/SWCLK-PA14_37") (pintype "passive"))
    )
    (net (code "106") (name "unconnected-(U9-JTMS{slash}SWDIO-PA13-Pad34)") (class "Default")
      (node (ref "U9") (pin "34") (pinfunction "JTMS/SWDIO-PA13_34") (pintype "passive"))
    )
    (net (code "107") (name "unconnected-(U10-JTCK{slash}SWCLK-PA14-Pad37)") (class "Default")
      (node (ref "U10") (pin "37") (pinfunction "JTCK/SWCLK-PA14_37") (pintype "passive"))
    )
    (net (code "108") (name "unconnected-(U10-JTMS{slash}SWDIO-PA13-Pad34)") (class "Default")
      (node (ref "U10") (pin "34") (pinfunction "JTMS/SWDIO-PA13_34") (pintype "passive"))
    )
    (net (code "109") (name "unconnected-(U11-ADC-Pad2)") (class "Default")
      (node (ref "U11") (pin "2") (pinfunction "ADC_2") (pintype "passive"))
    )
    (net (code "110") (name "unconnected-(U11-C0-Pad9)") (class "Default")
      (node (ref "U11") (pin "9") (pinfunction "C0_9") (pintype "passive"))
    )
    (net (code "111") (name "unconnected-(U11-I9-Pad11)") (class "Default")
      (node (ref "U11") (pin "11") (pinfunction "I9_11") (pintype "passive"))
    )
    (net (code "112") (name "unconnected-(U11-I10-Pad12)") (class "Default")
      (node (ref "U11") (pin "12") (pinfunction "I10_12") (pintype "passive"))
    )
    (net (code "113") (name "unconnected-(U11-IO2-Pad17)") (class "Default")
      (node (ref "U11") (pin "17") (pinfunction "IO2_17") (pintype "passive"))
    )
    (net (code "114") (name "unconnected-(U11-IO4-Pad19)") (class "Default")
      (node (ref "U11") (pin "19") (pinfunction "IO4_19") (pintype "passive"))
    )
    (net (code "115") (name "unconnected-(U11-IO5-Pad20)") (class "Default")
      (node (ref "U11") (pin "20") (pinfunction "IO5_20") (pintype "passive"))
    )
    (net (code "116") (name "unconnected-(U11-IO12-Pad6)") (class "Default")
      (node (ref "U11") (pin "6") (pinfunction "IO12_6") (pintype "passive"))
    )
    (net (code "117") (name "unconnected-(U11-IO13-Pad7)") (class "Default")
      (node (ref "U11") (pin "7") (pinfunction "IO13_7") (pintype "passive"))
    )
    (net (code "118") (name "unconnected-(U11-IO14-Pad5)") (class "Default")
      (node (ref "U11") (pin "5") (pinfunction "IO14_5") (pintype "passive"))
    )
    (net (code "119") (name "unconnected-(U11-IO16-Pad4)") (class "Default")
      (node (ref "U11") (pin "4") (pinfunction "IO16_4") (pintype "passive"))
    )
    (net (code "120") (name "unconnected-(U11-MI-Pad13)") (class "Default")
      (node (ref "U11") (pin "13") (pinfunction "MI_13") (pintype "passive"))
    )
    (net (code "121") (name "unconnected-(U11-MO-Pad10)") (class "Default")
      (node (ref "U11") (pin "10") (pinfunction "MO_10") (pintype "passive"))
    )
    (net (code "122") (name "unconnected-(U11-SK-Pad14)") (class "Default")
      (node (ref "U11") (pin "14") (pinfunction "SK_14") (pintype "passive"))
    )
    (net (code "123") (name "控地") (class "Default")
      (node (ref "BEEP1") (pin "2") (pinfunction "GND_2") (pintype "passive"))
      (node (ref "C36") (pin "1") (pinfunction "1_1") (pintype "passive"))
      (node (ref "C37") (pin "1") (pinfunction "1_1") (pintype "passive"))
      (node (ref "C38") (pin "1") (pinfunction "1_1") (pintype "passive"))
      (node (ref "C39") (pin "1") (pinfunction "1_1") (pintype "passive"))
      (node (ref "C40") (pin "1") (pinfunction "1_1") (pintype "passive"))
      (node (ref "C41") (pin "1") (pinfunction "1_1") (pintype "passive"))
      (node (ref "C42") (pin "1") (pinfunction "1_1") (pintype "passive"))
      (node (ref "C43") (pin "1") (pinfunction "1_1") (pintype "passive"))
      (node (ref "C44") (pin "1") (pinfunction "1_1") (pintype "passive"))
      (node (ref "C45") (pin "1") (pinfunction "1_1") (pintype "passive"))
      (node (ref "C47") (pin "1") (pinfunction "1_1") (pintype "passive"))
      (node (ref "C48") (pin "1") (pinfunction "1_1") (pintype "passive"))
      (node (ref "C49") (pin "1") (pinfunction "1_1") (pintype "passive"))
      (node (ref "C50") (pin "1") (pinfunction "1_1") (pintype "passive"))
      (node (ref "C51") (pin "2") (pinfunction "2_2") (pintype "passive"))
      (node (ref "C52") (pin "2") (pinfunction "2_2") (pintype "passive"))
      (node (ref "C53") (pin "1") (pinfunction "1_1") (pintype "passive"))
      (node (ref "C54") (pin "1") (pinfunction "1_1") (pintype "passive"))
      (node (ref "C55") (pin "1") (pinfunction "1_1") (pintype "passive"))
      (node (ref "C56") (pin "1") (pinfunction "1_1") (pintype "passive"))
      (node (ref "C57") (pin "1") (pinfunction "1_1") (pintype "passive"))
      (node (ref "H7") (pin "1") (pintype "passive"))
      (node (ref "P1") (pin "1") (pinfunction "1_1") (pintype "passive"))
      (node (ref "P10") (pin "4") (pinfunction "4_4") (pintype "passive"))
      (node (ref "P11") (pin "4") (pinfunction "4_4") (pintype "passive"))
      (node (ref "P12") (pin "5") (pinfunction "5_5") (pintype "passive"))
      (node (ref "P12") (pin "6") (pinfunction "6_6") (pintype "passive"))
      (node (ref "P13") (pin "5") (pinfunction "5_5") (pintype "passive"))
      (node (ref "P13") (pin "6") (pinfunction "6_6") (pintype "passive"))
      (node (ref "P14") (pin "1") (pinfunction "1_1") (pintype "passive"))
      (node (ref "P14") (pin "5") (pinfunction "5_5") (pintype "passive"))
      (node (ref "P15") (pin "1") (pinfunction "1_1") (pintype "passive"))
      (node (ref "P15") (pin "5") (pinfunction "5_5") (pintype "passive"))
      (node (ref "P16") (pin "1") (pinfunction "1_1") (pintype "passive"))
      (node (ref "P17") (pin "1") (pinfunction "1_1") (pintype "passive"))
      (node (ref "P18") (pin "1") (pinfunction "1_1") (pintype "passive"))
      (node (ref "P19") (pin "1") (pinfunction "1_1") (pintype "passive"))
      (node (ref "P2") (pin "1") (pinfunction "1_1") (pintype "passive"))
      (node (ref "P2") (pin "17") (pinfunction "17_17") (pintype "passive"))
      (node (ref "P20") (pin "1") (pinfunction "1_1") (pintype "passive"))
      (node (ref "P21") (pin "1") (pinfunction "1_1") (pintype "passive"))
      (node (ref "P22") (pin "1") (pinfunction "1_1") (pintype "passive"))
      (node (ref "P23") (pin "1") (pinfunction "1_1") (pintype "passive"))
      (node (ref "P4") (pin "4") (pinfunction "4_4") (pintype "passive"))
      (node (ref "P5") (pin "1") (pinfunction "1_1") (pintype "passive"))
      (node (ref "P5") (pin "17") (pinfunction "17_17") (pintype "passive"))
      (node (ref "P6") (pin "1") (pinfunction "1_1") (pintype "passive"))
      (node (ref "P7") (pin "2") (pinfunction "2_2") (pintype "passive"))
      (node (ref "P8") (pin "1") (pinfunction "1_1") (pintype "passive"))
      (node (ref "R81") (pin "1") (pinfunction "1_1") (pintype "passive"))
      (node (ref "U10") (pin "23") (pinfunction "VSS_1_23") (pintype "passive"))
      (node (ref "U10") (pin "35") (pinfunction "VSS_2_35") (pintype "passive"))
      (node (ref "U10") (pin "47") (pinfunction "VSS_3_47") (pintype "passive"))
      (node (ref "U10") (pin "8") (pinfunction "VSSA_8") (pintype "passive"))
      (node (ref "U11") (pin "15") (pinfunction "GND_15") (pintype "passive"))
      (node (ref "U9") (pin "23") (pinfunction "VSS_1_23") (pintype "passive"))
      (node (ref "U9") (pin "35") (pinfunction "VSS_2_35") (pintype "passive"))
      (node (ref "U9") (pin "47") (pinfunction "VSS_3_47") (pintype "passive"))
      (node (ref "U9") (pin "8") (pinfunction "VSSA_8") (pintype "passive"))
      (node (ref "key1") (pin "2") (pinfunction "2_2") (pintype "passive"))
      (node (ref "key2") (pin "2") (pinfunction "2_2") (pintype "passive"))
    )
  )
)
